# OpenEVSE_PLUS_v4.net
KiCad netlist of a schematic drawn in EAGLE
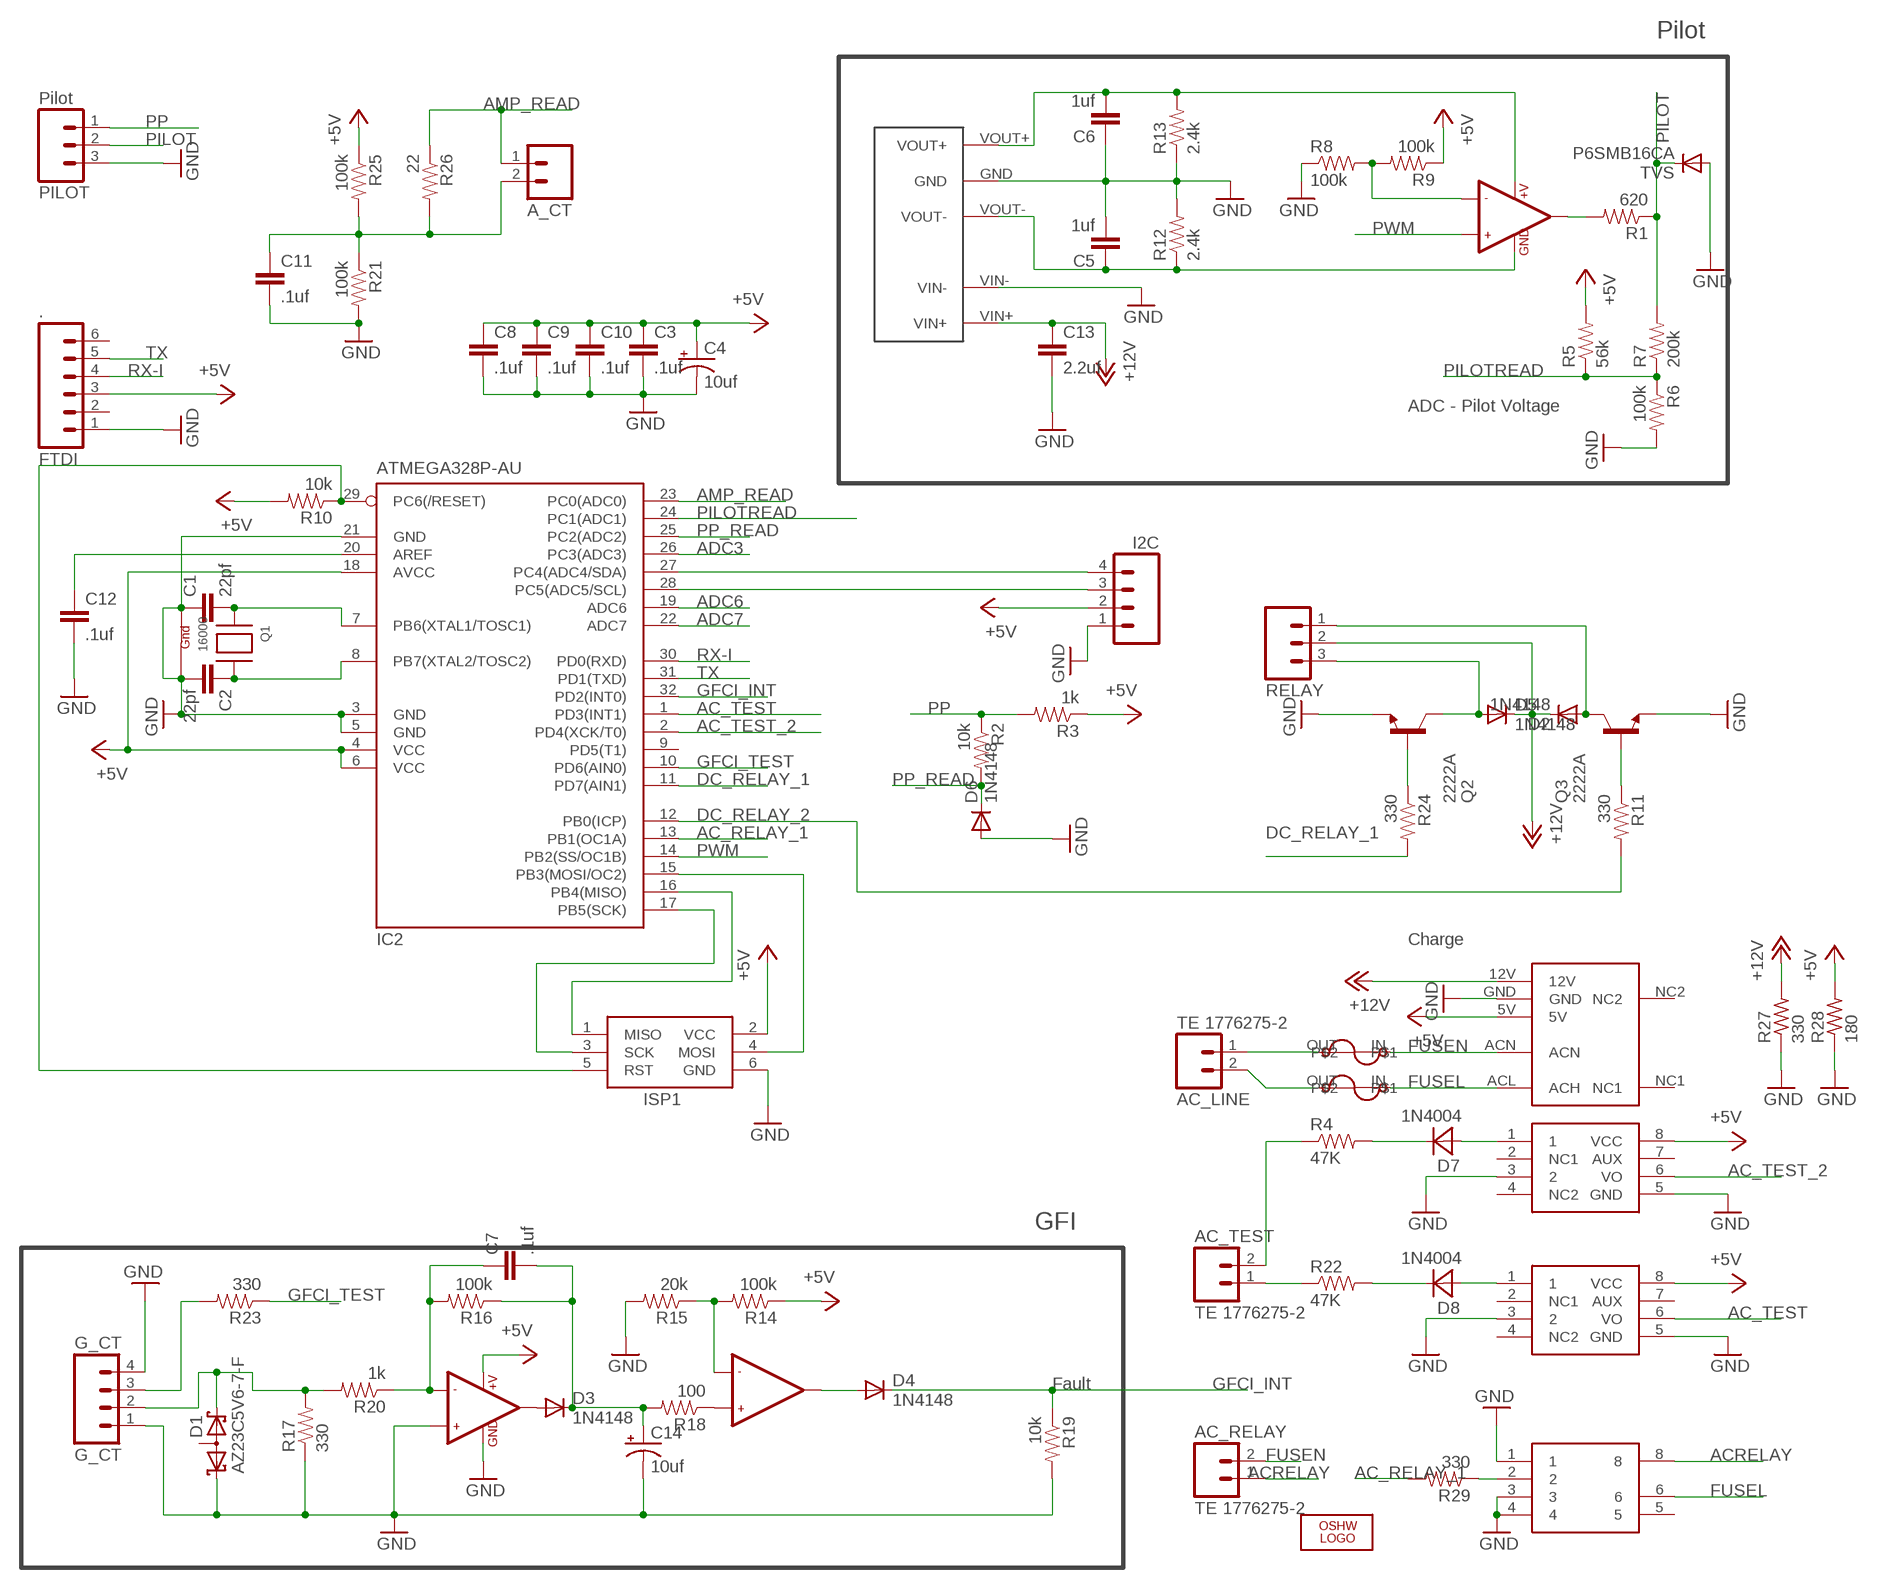
[diagram p0: schematic, sheet 1]

(export (version "E")
  (design (tool "Eeschema 10.0.6"))
  (components
    (comp (ref ".")
      (value "FTDI")
      (footprint "eagle-import:1X06_LOCK")
      (libsource (lib "eagle-import") (part "M06LOCK"))
    )
    (comp (ref "AC_LINE")
      (value "TE 1776275-2")
      (footprint "eagle-import:SCREWTERMINAL-3.5MM-2_LOCK")
      (libsource (lib "eagle-import") (part "M023.5MM_LOCK"))
    )
    (comp (ref "AC_RELAY")
      (value "TE 1776275-2")
      (footprint "eagle-import:SCREWTERMINAL-3.5MM-2_LOCK")
      (libsource (lib "eagle-import") (part "M023.5MM_LOCK"))
    )
    (comp (ref "AC_TEST")
      (value "TE 1776275-2")
      (footprint "eagle-import:SCREWTERMINAL-3.5MM-2_LOCK")
      (libsource (lib "eagle-import") (part "M023.5MM_LOCK"))
    )
    (comp (ref "A_CT")
      (value "M02PTH")
      (footprint "eagle-import:1X02")
      (libsource (lib "eagle-import") (part "M02PTH"))
    )
    (comp (ref "C1")
      (value "22pf")
      (footprint "eagle-import:0805")
      (libsource (lib "eagle-import") (part "CAP0805"))
    )
    (comp (ref "C2")
      (value "22pf")
      (footprint "eagle-import:0805")
      (libsource (lib "eagle-import") (part "CAP0805"))
    )
    (comp (ref "C3")
      (value ".1uf")
      (footprint "eagle-import:0805")
      (libsource (lib "eagle-import") (part "CAP0805"))
    )
    (comp (ref "C4")
      (value "10uf")
      (footprint "eagle-import:EIA3216")
      (libsource (lib "eagle-import") (part "CAP_POL1206"))
    )
    (comp (ref "C5")
      (value "1uf")
      (footprint "eagle-import:0805")
      (libsource (lib "eagle-import") (part "CAP0805"))
    )
    (comp (ref "C6")
      (value "1uf")
      (footprint "eagle-import:0805")
      (libsource (lib "eagle-import") (part "CAP0805"))
    )
    (comp (ref "C7")
      (value ".1uf")
      (footprint "eagle-import:0805")
      (libsource (lib "eagle-import") (part "CAP0805"))
    )
    (comp (ref "C8")
      (value ".1uf")
      (footprint "eagle-import:0805")
      (libsource (lib "eagle-import") (part "CAP0805"))
    )
    (comp (ref "C9")
      (value ".1uf")
      (footprint "eagle-import:0805")
      (libsource (lib "eagle-import") (part "CAP0805"))
    )
    (comp (ref "C10")
      (value ".1uf")
      (footprint "eagle-import:0805")
      (libsource (lib "eagle-import") (part "CAP0805"))
    )
    (comp (ref "C11")
      (value ".1uf")
      (footprint "eagle-import:0805")
      (libsource (lib "eagle-import") (part "CAP0805"))
    )
    (comp (ref "C12")
      (value ".1uf")
      (footprint "eagle-import:0805")
      (libsource (lib "eagle-import") (part "CAP0805"))
    )
    (comp (ref "C13")
      (value "2.2uf")
      (footprint "eagle-import:0805")
      (libsource (lib "eagle-import") (part "CAP0805"))
    )
    (comp (ref "C14")
      (value "10uf")
      (footprint "eagle-import:EIA3216")
      (libsource (lib "eagle-import") (part "CAP_POL1206"))
    )
    (comp (ref "D1")
      (value "AZ23C5V6-7-F")
      (footprint "eagle-import:SOT23")
      (libsource (lib "eagle-import") (part "BAS40-06"))
    )
    (comp (ref "D2")
      (value "1N4148")
      (footprint "eagle-import:SOD123")
      (libsource (lib "eagle-import") (part "DIODE-SOD123"))
    )
    (comp (ref "D3")
      (value "1N4148")
      (footprint "eagle-import:SOD123")
      (libsource (lib "eagle-import") (part "DIODE-SOD123"))
    )
    (comp (ref "D4")
      (value "1N4148")
      (footprint "eagle-import:SOD123")
      (libsource (lib "eagle-import") (part "DIODE-SOD123"))
    )
    (comp (ref "D5")
      (value "1N4148")
      (footprint "eagle-import:SOD123")
      (libsource (lib "eagle-import") (part "DIODE-SOD123"))
    )
    (comp (ref "D6")
      (value "1N4148")
      (footprint "eagle-import:SOD123")
      (libsource (lib "eagle-import") (part "DIODE-SOD123"))
    )
    (comp (ref "D7")
      (value "1N4004")
      (footprint "eagle-import:SMA")
      (libsource (lib "eagle-import") (part "MBRA340T3"))
    )
    (comp (ref "D8")
      (value "1N4004")
      (footprint "eagle-import:SMA")
      (libsource (lib "eagle-import") (part "MBRA340T3"))
    )
    (comp (ref "DCDC")
      (value "MD112D-12E")
      (footprint "eagle-import:DCDC_SIP")
      (libsource (lib "eagle-import") (part "DCDC_SIP"))
    )
    (comp (ref "F1")
      (value "BEL1AFUSE")
      (footprint "eagle-import:BELFUSE1A")
      (libsource (lib "eagle-import") (part "BEL1AFUSE"))
    )
    (comp (ref "F2")
      (value "BEL1AFUSE")
      (footprint "eagle-import:BELFUSE1A")
      (libsource (lib "eagle-import") (part "BEL1AFUSE"))
    )
    (comp (ref "G_CT")
      (value "G_CT")
      (footprint "eagle-import:1X04_LOCK")
      (libsource (lib "eagle-import") (part "M04LOCK"))
    )
    (comp (ref "I2C")
      (value "M04LOCK")
      (footprint "eagle-import:1X04_LOCK")
      (libsource (lib "eagle-import") (part "M04LOCK"))
    )
    (comp (ref "IC1")
      (value "MID400")
      (footprint "eagle-import:DIP08")
      (libsource (lib "eagle-import") (part "MID400"))
    )
    (comp (ref "IC2")
      (value "ATMEGA328P-AU")
      (footprint "eagle-import:TQFP32-08")
      (fields (field (name "MPN") "ATMEGA8-16AU"))
      (libsource (lib "eagle-import") (part "MEGA8-AI"))
    )
    (comp (ref "IC3")
      (value "LM358")
      (footprint "eagle-import:SO08")
      (libsource (lib "eagle-import") (part "LMV358"))
    )
    (comp (ref "IC4")
      (value "LF353")
      (footprint "eagle-import:SO08")
      (libsource (lib "eagle-import") (part "LMV358"))
    )
    (comp (ref "IC5")
      (value "AQH1213")
      (footprint "eagle-import:DIP7")
      (libsource (lib "eagle-import") (part "AQH1213"))
    )
    (comp (ref "IC6")
      (value "MID400")
      (footprint "eagle-import:DIP08")
      (libsource (lib "eagle-import") (part "MID400"))
    )
    (comp (ref "ISP1")
      (value "AVRISP-6")
      (footprint "eagle-import:AVRISP")
      (libsource (lib "eagle-import") (part "AVRISP-6"))
    )
    (comp (ref "LOGO1")
      (value "OSHW_LOGO_8MILX0150-NT")
      (footprint "eagle-import:OSHW_8X150_NOTEXT")
      (libsource (lib "eagle-import") (part "OSHW_LOGO_8MILX0150-NT"))
    )
    (comp (ref "PILOT")
      (value "Pilot")
      (footprint "eagle-import:SCREWTERMINAL-3.5MM-3_LOCK.007S")
      (libsource (lib "eagle-import") (part "M03SCREW_LOCK"))
    )
    (comp (ref "Q1")
      (value "16000")
      (footprint "eagle-import:NX3225")
      (libsource (lib "eagle-import") (part "XTAL-4-3225"))
    )
    (comp (ref "Q2")
      (value "2222A")
      (footprint "eagle-import:SOT23")
      (libsource (lib "eagle-import") (part "BCX70SMD"))
    )
    (comp (ref "Q3")
      (value "2222A")
      (footprint "eagle-import:SOT23")
      (libsource (lib "eagle-import") (part "BCX70SMD"))
    )
    (comp (ref "R1")
      (value "620")
      (footprint "eagle-import:0805")
      (libsource (lib "eagle-import") (part "RESISTOR0805-RES"))
    )
    (comp (ref "R2")
      (value "10k")
      (footprint "eagle-import:0805")
      (libsource (lib "eagle-import") (part "RESISTOR0805-RES"))
    )
    (comp (ref "R3")
      (value "1k")
      (footprint "eagle-import:0805")
      (libsource (lib "eagle-import") (part "RESISTOR0805-RES"))
    )
    (comp (ref "R4")
      (value "47K")
      (footprint "eagle-import:AXIAL-0.4")
      (libsource (lib "eagle-import") (part "RESISTORPTH-1/4W"))
    )
    (comp (ref "R5")
      (value "56k")
      (footprint "eagle-import:0805")
      (libsource (lib "eagle-import") (part "RESISTOR0805-RES"))
    )
    (comp (ref "R6")
      (value "100k")
      (footprint "eagle-import:0805")
      (libsource (lib "eagle-import") (part "RESISTOR0805-RES"))
    )
    (comp (ref "R7")
      (value "200k")
      (footprint "eagle-import:0805")
      (libsource (lib "eagle-import") (part "RESISTOR0805-RES"))
    )
    (comp (ref "R8")
      (value "100k")
      (footprint "eagle-import:0805")
      (libsource (lib "eagle-import") (part "RESISTOR0805-RES"))
    )
    (comp (ref "R9")
      (value "100k")
      (footprint "eagle-import:0805")
      (libsource (lib "eagle-import") (part "RESISTOR0805-RES"))
    )
    (comp (ref "R10")
      (value "10k")
      (footprint "eagle-import:0805")
      (libsource (lib "eagle-import") (part "RESISTOR0805-RES"))
    )
    (comp (ref "R11")
      (value "330")
      (footprint "eagle-import:0805")
      (libsource (lib "eagle-import") (part "RESISTOR0805-RES"))
    )
    (comp (ref "R12")
      (value "2.4k")
      (footprint "eagle-import:0805")
      (libsource (lib "eagle-import") (part "RESISTOR0805-RES"))
    )
    (comp (ref "R13")
      (value "2.4k")
      (footprint "eagle-import:0805")
      (libsource (lib "eagle-import") (part "RESISTOR0805-RES"))
    )
    (comp (ref "R14")
      (value "100k")
      (footprint "eagle-import:0805")
      (libsource (lib "eagle-import") (part "RESISTOR0805-RES"))
    )
    (comp (ref "R15")
      (value "20k")
      (footprint "eagle-import:0805")
      (libsource (lib "eagle-import") (part "RESISTOR0805-RES"))
    )
    (comp (ref "R16")
      (value "100k")
      (footprint "eagle-import:0805")
      (libsource (lib "eagle-import") (part "RESISTOR0805-RES"))
    )
    (comp (ref "R17")
      (value "330")
      (footprint "eagle-import:0805")
      (libsource (lib "eagle-import") (part "RESISTOR0805-RES"))
    )
    (comp (ref "R18")
      (value "100")
      (footprint "eagle-import:0805")
      (libsource (lib "eagle-import") (part "RESISTOR0805-RES"))
    )
    (comp (ref "R19")
      (value "10k")
      (footprint "eagle-import:0805")
      (libsource (lib "eagle-import") (part "RESISTOR0805-RES"))
    )
    (comp (ref "R20")
      (value "1k")
      (footprint "eagle-import:0805")
      (libsource (lib "eagle-import") (part "RESISTOR0805-RES"))
    )
    (comp (ref "R21")
      (value "100k")
      (footprint "eagle-import:0805")
      (libsource (lib "eagle-import") (part "RESISTOR0805-RES"))
    )
    (comp (ref "R22")
      (value "47K")
      (footprint "eagle-import:AXIAL-0.4")
      (libsource (lib "eagle-import") (part "RESISTORPTH-1/4W"))
    )
    (comp (ref "R23")
      (value "330")
      (footprint "eagle-import:0805")
      (libsource (lib "eagle-import") (part "RESISTOR0805-RES"))
    )
    (comp (ref "R24")
      (value "330")
      (footprint "eagle-import:0805")
      (libsource (lib "eagle-import") (part "RESISTOR0805-RES"))
    )
    (comp (ref "R25")
      (value "100k")
      (footprint "eagle-import:0805")
      (libsource (lib "eagle-import") (part "RESISTOR0805-RES"))
    )
    (comp (ref "R26")
      (value "22")
      (footprint "eagle-import:0805")
      (libsource (lib "eagle-import") (part "RESISTOR0805-RES"))
    )
    (comp (ref "R27")
      (value "330")
      (footprint "eagle-import:R1206")
      (libsource (lib "eagle-import") (part "R-US_R1206"))
    )
    (comp (ref "R28")
      (value "180")
      (footprint "eagle-import:R1206")
      (libsource (lib "eagle-import") (part "R-US_R1206"))
    )
    (comp (ref "R29")
      (value "330")
      (footprint "eagle-import:0805")
      (libsource (lib "eagle-import") (part "RESISTOR0805-RES"))
    )
    (comp (ref "RELAY")
      (value "M03SCREW_LOCK")
      (footprint "eagle-import:SCREWTERMINAL-3.5MM-3_LOCK.007S")
      (libsource (lib "eagle-import") (part "M03SCREW_LOCK"))
    )
    (comp (ref "TVS")
      (value "P6SMB16CA")
      (footprint "eagle-import:SMB")
      (libsource (lib "eagle-import") (part "DIODE-SMB"))
    )
    (comp (ref "U$1")
      (value "MPM-04E-1205")
      (footprint "eagle-import:MPM-04E-1205")
      (libsource (lib "eagle-import") (part "MPM-04E-1205"))
    )
  )
  (nets
    (net (code "1") (name "+5V") (class "Default")
      (node (ref ".") (pin "3") (pinfunction "3_3") (pintype "passive"))
      (node (ref "C10") (pin "1") (pinfunction "1_1") (pintype "passive"))
      (node (ref "C3") (pin "1") (pinfunction "1_1") (pintype "passive"))
      (node (ref "C4") (pin "A") (pinfunction "+_A") (pintype "passive"))
      (node (ref "C8") (pin "1") (pinfunction "1_1") (pintype "passive"))
      (node (ref "C9") (pin "1") (pinfunction "1_1") (pintype "passive"))
      (node (ref "I2C") (pin "2") (pinfunction "2_2") (pintype "passive"))
      (node (ref "IC1") (pin "8") (pinfunction "VCC_8") (pintype "bidirectional"))
      (node (ref "IC2") (pin "18") (pinfunction "AVCC_18") (pintype "power_in"))
      (node (ref "IC2") (pin "4") (pinfunction "VCC_4") (pintype "power_in"))
      (node (ref "IC2") (pin "6") (pinfunction "VCC_6") (pintype "power_in"))
      (node (ref "IC3") (pin "8") (pinfunction "+V_8") (pintype "power_in"))
      (node (ref "IC6") (pin "8") (pinfunction "VCC_8") (pintype "bidirectional"))
      (node (ref "ISP1") (pin "2") (pinfunction "VCC_2") (pintype "power_in"))
      (node (ref "R10") (pin "2") (pinfunction "2_2") (pintype "passive"))
      (node (ref "R14") (pin "1") (pinfunction "1_1") (pintype "passive"))
      (node (ref "R25") (pin "1") (pinfunction "1_1") (pintype "passive"))
      (node (ref "R28") (pin "2") (pinfunction "2_2") (pintype "passive"))
      (node (ref "R3") (pin "1") (pinfunction "1_1") (pintype "passive"))
      (node (ref "R5") (pin "2") (pinfunction "2_2") (pintype "passive"))
      (node (ref "R9") (pin "1") (pinfunction "1_1") (pintype "passive"))
      (node (ref "U$1") (pin "5V") (pinfunction "5V_5V") (pintype "bidirectional"))
    )
    (net (code "2") (name "+12V") (class "Default")
      (node (ref "C13") (pin "1") (pinfunction "1_1") (pintype "passive"))
      (node (ref "D2") (pin "C") (pinfunction "C_C") (pintype "passive"))
      (node (ref "D5") (pin "C") (pinfunction "C_C") (pintype "passive"))
      (node (ref "DCDC") (pin "VIN+") (pinfunction "VIN+_VIN+") (pintype "bidirectional"))
      (node (ref "R27") (pin "2") (pinfunction "2_2") (pintype "passive"))
      (node (ref "RELAY") (pin "2") (pinfunction "2_2") (pintype "passive"))
      (node (ref "U$1") (pin "12V") (pinfunction "12V_12V") (pintype "bidirectional"))
    )
    (net (code "3") (name "/ACRELAY") (class "Default")
      (node (ref "AC_RELAY") (pin "1") (pinfunction "1_1") (pintype "passive"))
      (node (ref "IC5") (pin "8") (pinfunction "8_8") (pintype "bidirectional"))
    )
    (net (code "4") (name "/AC_RELAY_1") (class "Default")
      (node (ref "IC2") (pin "13") (pinfunction "PB1(OC1A)_13") (pintype "bidirectional"))
      (node (ref "R29") (pin "2") (pinfunction "2_2") (pintype "passive"))
    )
    (net (code "5") (name "/AC_TEST") (class "Default")
      (node (ref "IC2") (pin "1") (pinfunction "PD3(INT1)_1") (pintype "bidirectional"))
      (node (ref "IC6") (pin "6") (pinfunction "VO_6") (pintype "bidirectional"))
    )
    (net (code "6") (name "/AC_TEST_2") (class "Default")
      (node (ref "IC1") (pin "6") (pinfunction "VO_6") (pintype "bidirectional"))
      (node (ref "IC2") (pin "2") (pinfunction "PD4(XCK/T0)_2") (pintype "bidirectional"))
    )
    (net (code "7") (name "/ADC3") (class "Default")
      (node (ref "IC2") (pin "26") (pinfunction "PC3(ADC3)_26") (pintype "bidirectional"))
    )
    (net (code "8") (name "/ADC6") (class "Default")
      (node (ref "IC2") (pin "19") (pinfunction "ADC6_19") (pintype "bidirectional"))
    )
    (net (code "9") (name "/ADC7") (class "Default")
      (node (ref "IC2") (pin "22") (pinfunction "ADC7_22") (pintype "bidirectional"))
    )
    (net (code "10") (name "/AMP_READ") (class "Default")
      (node (ref "A_CT") (pin "1") (pinfunction "1_1") (pintype "passive"))
      (node (ref "IC2") (pin "23") (pinfunction "PC0(ADC0)_23") (pintype "bidirectional"))
      (node (ref "R26") (pin "1") (pinfunction "1_1") (pintype "passive"))
    )
    (net (code "11") (name "/DC_RELAY_1") (class "Default")
      (node (ref "IC2") (pin "11") (pinfunction "PD7(AIN1)_11") (pintype "bidirectional"))
      (node (ref "R24") (pin "2") (pinfunction "2_2") (pintype "passive"))
    )
    (net (code "12") (name "/DC_RELAY_2") (class "Default")
      (node (ref "IC2") (pin "12") (pinfunction "PB0(ICP)_12") (pintype "bidirectional"))
      (node (ref "R11") (pin "2") (pinfunction "2_2") (pintype "passive"))
    )
    (net (code "13") (name "/FUSEL") (class "Default")
      (node (ref "F2") (pin "IN") (pinfunction "P$2_IN") (pintype "bidirectional"))
      (node (ref "IC5") (pin "6") (pinfunction "6_6") (pintype "bidirectional"))
      (node (ref "U$1") (pin "ACL") (pinfunction "ACH_ACL") (pintype "bidirectional"))
    )
    (net (code "14") (name "/FUSEN") (class "Default")
      (node (ref "AC_RELAY") (pin "2") (pinfunction "2_2") (pintype "passive"))
      (node (ref "F1") (pin "IN") (pinfunction "P$2_IN") (pintype "bidirectional"))
      (node (ref "U$1") (pin "ACN") (pinfunction "ACN_ACN") (pintype "bidirectional"))
    )
    (net (code "15") (name "/GFCI_INT") (class "Default")
      (node (ref "D4") (pin "C") (pinfunction "C_C") (pintype "passive"))
      (node (ref "IC2") (pin "32") (pinfunction "PD2(INT0)_32") (pintype "bidirectional"))
      (node (ref "R19") (pin "1") (pinfunction "1_1") (pintype "passive"))
    )
    (net (code "16") (name "/GFCI_TEST") (class "Default")
      (node (ref "IC2") (pin "10") (pinfunction "PD6(AIN0)_10") (pintype "bidirectional"))
      (node (ref "R23") (pin "1") (pinfunction "1_1") (pintype "passive"))
    )
    (net (code "17") (name "/PILOT") (class "Default")
      (node (ref "PILOT") (pin "2") (pinfunction "2_2") (pintype "passive"))
      (node (ref "R1") (pin "1") (pinfunction "1_1") (pintype "passive"))
      (node (ref "R7") (pin "2") (pinfunction "2_2") (pintype "passive"))
      (node (ref "TVS") (pin "C") (pinfunction "C_C") (pintype "passive"))
    )
    (net (code "18") (name "/PILOTREAD") (class "Default")
      (node (ref "IC2") (pin "24") (pinfunction "PC1(ADC1)_24") (pintype "bidirectional"))
      (node (ref "R5") (pin "1") (pinfunction "1_1") (pintype "passive"))
      (node (ref "R6") (pin "1") (pinfunction "1_1") (pintype "passive"))
      (node (ref "R7") (pin "1") (pinfunction "1_1") (pintype "passive"))
    )
    (net (code "19") (name "/PP") (class "Default")
      (node (ref "PILOT") (pin "1") (pinfunction "1_1") (pintype "passive"))
      (node (ref "R2") (pin "1") (pinfunction "1_1") (pintype "passive"))
      (node (ref "R3") (pin "2") (pinfunction "2_2") (pintype "passive"))
    )
    (net (code "20") (name "/PP_READ") (class "Default")
      (node (ref "D6") (pin "C") (pinfunction "C_C") (pintype "passive"))
      (node (ref "IC2") (pin "25") (pinfunction "PC2(ADC2)_25") (pintype "bidirectional"))
      (node (ref "R2") (pin "2") (pinfunction "2_2") (pintype "passive"))
    )
    (net (code "21") (name "/PWM") (class "Default")
      (node (ref "IC2") (pin "14") (pinfunction "PB2(SS/OC1B)_14") (pintype "bidirectional"))
      (node (ref "IC4") (pin "3") (pinfunction "+IN1_3") (pintype "input"))
    )
    (net (code "22") (name "/RX-I") (class "Default")
      (node (ref ".") (pin "4") (pinfunction "4_4") (pintype "passive"))
      (node (ref "IC2") (pin "30") (pinfunction "PD0(RXD)_30") (pintype "bidirectional"))
    )
    (net (code "23") (name "/TX") (class "Default")
      (node (ref ".") (pin "5") (pinfunction "5_5") (pintype "passive"))
      (node (ref "IC2") (pin "31") (pinfunction "PD1(TXD)_31") (pintype "bidirectional"))
    )
    (net (code "24") (name "GND") (class "Default")
      (node (ref ".") (pin "1") (pinfunction "1_1") (pintype "passive"))
      (node (ref "C1") (pin "1") (pinfunction "1_1") (pintype "passive"))
      (node (ref "C10") (pin "2") (pinfunction "2_2") (pintype "passive"))
      (node (ref "C11") (pin "2") (pinfunction "2_2") (pintype "passive"))
      (node (ref "C12") (pin "2") (pinfunction "2_2") (pintype "passive"))
      (node (ref "C13") (pin "2") (pinfunction "2_2") (pintype "passive"))
      (node (ref "C14") (pin "C") (pinfunction "-_C") (pintype "passive"))
      (node (ref "C2") (pin "2") (pinfunction "2_2") (pintype "passive"))
      (node (ref "C3") (pin "2") (pinfunction "2_2") (pintype "passive"))
      (node (ref "C4") (pin "C") (pinfunction "-_C") (pintype "passive"))
      (node (ref "C5") (pin "2") (pinfunction "2_2") (pintype "passive"))
      (node (ref "C6") (pin "1") (pinfunction "1_1") (pintype "passive"))
      (node (ref "C8") (pin "2") (pinfunction "2_2") (pintype "passive"))
      (node (ref "C9") (pin "2") (pinfunction "2_2") (pintype "passive"))
      (node (ref "D1") (pin "1") (pinfunction "K1_1") (pintype "passive"))
      (node (ref "D6") (pin "A") (pinfunction "A_A") (pintype "passive"))
      (node (ref "DCDC") (pin "GND") (pinfunction "GND_GND") (pintype "bidirectional"))
      (node (ref "DCDC") (pin "VIN-") (pinfunction "VIN-_VIN-") (pintype "bidirectional"))
      (node (ref "G_CT") (pin "1") (pinfunction "1_1") (pintype "passive"))
      (node (ref "G_CT") (pin "4") (pinfunction "4_4") (pintype "passive"))
      (node (ref "I2C") (pin "1") (pinfunction "1_1") (pintype "passive"))
      (node (ref "IC1") (pin "3") (pinfunction "2_3") (pintype "bidirectional"))
      (node (ref "IC1") (pin "5") (pinfunction "GND_5") (pintype "bidirectional"))
      (node (ref "IC2") (pin "21") (pinfunction "GND_21") (pintype "power_in"))
      (node (ref "IC2") (pin "3") (pinfunction "GND_3") (pintype "power_in"))
      (node (ref "IC2") (pin "5") (pinfunction "GND_5") (pintype "power_in"))
      (node (ref "IC3") (pin "3") (pinfunction "+IN1_3") (pintype "input"))
      (node (ref "IC3") (pin "4") (pinfunction "GND_4") (pintype "power_in"))
      (node (ref "IC5") (pin "1") (pinfunction "1_1") (pintype "bidirectional"))
      (node (ref "IC5") (pin "3") (pinfunction "3_3") (pintype "bidirectional"))
      (node (ref "IC5") (pin "4") (pinfunction "4_4") (pintype "bidirectional"))
      (node (ref "IC6") (pin "3") (pinfunction "2_3") (pintype "bidirectional"))
      (node (ref "IC6") (pin "5") (pinfunction "GND_5") (pintype "bidirectional"))
      (node (ref "ISP1") (pin "6") (pinfunction "GND_6") (pintype "power_in"))
      (node (ref "PILOT") (pin "3") (pinfunction "3_3") (pintype "passive"))
      (node (ref "Q1") (pin "1") (pinfunction "G1_1") (pintype "power_in"))
      (node (ref "Q1") (pin "3") (pinfunction "G2_3") (pintype "power_in"))
      (node (ref "Q2") (pin "2") (pinfunction "E_2") (pintype "passive"))
      (node (ref "Q3") (pin "2") (pinfunction "E_2") (pintype "passive"))
      (node (ref "R12") (pin "2") (pinfunction "2_2") (pintype "passive"))
      (node (ref "R13") (pin "1") (pinfunction "1_1") (pintype "passive"))
      (node (ref "R15") (pin "2") (pinfunction "2_2") (pintype "passive"))
      (node (ref "R17") (pin "1") (pinfunction "1_1") (pintype "passive"))
      (node (ref "R19") (pin "2") (pinfunction "2_2") (pintype "passive"))
      (node (ref "R21") (pin "2") (pinfunction "2_2") (pintype "passive"))
      (node (ref "R27") (pin "1") (pinfunction "1_1") (pintype "passive"))
      (node (ref "R28") (pin "1") (pinfunction "1_1") (pintype "passive"))
      (node (ref "R6") (pin "2") (pinfunction "2_2") (pintype "passive"))
      (node (ref "R8") (pin "1") (pinfunction "1_1") (pintype "passive"))
      (node (ref "TVS") (pin "A") (pinfunction "A_A") (pintype "passive"))
      (node (ref "U$1") (pin "GND") (pinfunction "GND_GND") (pintype "bidirectional"))
    )
    (net (code "25") (name "Net-(A_CT-Pad2)") (class "Default")
      (node (ref "A_CT") (pin "2") (pinfunction "2_2") (pintype "passive"))
      (node (ref "C11") (pin "1") (pinfunction "1_1") (pintype "passive"))
      (node (ref "R21") (pin "1") (pinfunction "1_1") (pintype "passive"))
      (node (ref "R25") (pin "2") (pinfunction "2_2") (pintype "passive"))
      (node (ref "R26") (pin "2") (pinfunction "2_2") (pintype "passive"))
    )
    (net (code "26") (name "Net-(C14-+)") (class "Default")
      (node (ref "C14") (pin "A") (pinfunction "+_A") (pintype "passive"))
      (node (ref "C7") (pin "2") (pinfunction "2_2") (pintype "passive"))
      (node (ref "D3") (pin "C") (pinfunction "C_C") (pintype "passive"))
      (node (ref "R16") (pin "1") (pinfunction "1_1") (pintype "passive"))
      (node (ref "R18") (pin "2") (pinfunction "2_2") (pintype "passive"))
    )
    (net (code "27") (name "Net-(D1-K2)") (class "Default")
      (node (ref "D1") (pin "2") (pinfunction "K2_2") (pintype "passive"))
      (node (ref "G_CT") (pin "2") (pinfunction "2_2") (pintype "passive"))
      (node (ref "R17") (pin "2") (pinfunction "2_2") (pintype "passive"))
      (node (ref "R20") (pin "2") (pinfunction "2_2") (pintype "passive"))
    )
    (net (code "28") (name "Net-(D7-PadA)") (class "Default")
      (node (ref "D7") (pin "A") (pinfunction "A_A") (pintype "passive"))
      (node (ref "IC1") (pin "1") (pinfunction "1_1") (pintype "bidirectional"))
    )
    (net (code "29") (name "Net-(D8-PadA)") (class "Default")
      (node (ref "D8") (pin "A") (pinfunction "A_A") (pintype "passive"))
      (node (ref "IC6") (pin "1") (pinfunction "1_1") (pintype "bidirectional"))
    )
    (net (code "30") (name "Net-(F1-P$1)") (class "Default")
      (node (ref "AC_LINE") (pin "1") (pinfunction "1_1") (pintype "passive"))
      (node (ref "F1") (pin "OUT") (pinfunction "P$1_OUT") (pintype "bidirectional"))
    )
    (net (code "31") (name "Net-(F2-P$1)") (class "Default")
      (node (ref "AC_LINE") (pin "2") (pinfunction "2_2") (pintype "passive"))
      (node (ref "F2") (pin "OUT") (pinfunction "P$1_OUT") (pintype "bidirectional"))
    )
    (net (code "32") (name "Net-(G_CT-Pad3)") (class "Default")
      (node (ref "G_CT") (pin "3") (pinfunction "3_3") (pintype "passive"))
      (node (ref "R23") (pin "2") (pinfunction "2_2") (pintype "passive"))
    )
    (net (code "33") (name "Net-(IC2-AREF)") (class "Default")
      (node (ref "C12") (pin "1") (pinfunction "1_1") (pintype "passive"))
      (node (ref "IC2") (pin "20") (pinfunction "AREF_20") (pintype "passive"))
    )
    (net (code "34") (name "Net-(IC2-PB3(MOSI{slash}OC2))") (class "Default")
      (node (ref "IC2") (pin "15") (pinfunction "PB3(MOSI/OC2)_15") (pintype "bidirectional"))
      (node (ref "ISP1") (pin "4") (pinfunction "MOSI_4") (pintype "output"))
    )
    (net (code "35") (name "Net-(IC2-PB4(MISO))") (class "Default")
      (node (ref "IC2") (pin "16") (pinfunction "PB4(MISO)_16") (pintype "bidirectional"))
      (node (ref "ISP1") (pin "1") (pinfunction "MISO_1") (pintype "input"))
    )
    (net (code "36") (name "Net-(IC2-PB5(SCK))") (class "Default")
      (node (ref "IC2") (pin "17") (pinfunction "PB5(SCK)_17") (pintype "bidirectional"))
      (node (ref "ISP1") (pin "3") (pinfunction "SCK_3") (pintype "output"))
    )
    (net (code "37") (name "Net-(IC2-PB6(XTAL1{slash}TOSC1))") (class "Default")
      (node (ref "C1") (pin "2") (pinfunction "2_2") (pintype "passive"))
      (node (ref "IC2") (pin "7") (pinfunction "PB6(XTAL1/TOSC1)_7") (pintype "bidirectional"))
      (node (ref "Q1") (pin "2") (pinfunction "X1_2") (pintype "bidirectional"))
    )
    (net (code "38") (name "Net-(IC2-PB7(XTAL2{slash}TOSC2))") (class "Default")
      (node (ref "C2") (pin "1") (pinfunction "1_1") (pintype "passive"))
      (node (ref "IC2") (pin "8") (pinfunction "PB7(XTAL2/TOSC2)_8") (pintype "bidirectional"))
      (node (ref "Q1") (pin "4") (pinfunction "X2_4") (pintype "bidirectional"))
    )
    (net (code "39") (name "Net-(IC2-PC4(ADC4{slash}SDA))") (class "Default")
      (node (ref "I2C") (pin "4") (pinfunction "4_4") (pintype "passive"))
      (node (ref "IC2") (pin "27") (pinfunction "PC4(ADC4/SDA)_27") (pintype "bidirectional"))
    )
    (net (code "40") (name "Net-(IC2-PC5(ADC5{slash}SCL))") (class "Default")
      (node (ref "I2C") (pin "3") (pinfunction "3_3") (pintype "passive"))
      (node (ref "IC2") (pin "28") (pinfunction "PC5(ADC5/SCL)_28") (pintype "bidirectional"))
    )
    (net (code "41") (name "Net-(IC2-PC6({slash}RESET))") (class "Default")
      (node (ref "IC2") (pin "29") (pinfunction "PC6(/RESET)_29") (pintype "bidirectional"))
      (node (ref "ISP1") (pin "5") (pinfunction "RST_5") (pintype "output"))
      (node (ref "R10") (pin "1") (pinfunction "1_1") (pintype "passive"))
    )
    (net (code "42") (name "Net-(IC3A--IN1)") (class "Default")
      (node (ref "C7") (pin "1") (pinfunction "1_1") (pintype "passive"))
      (node (ref "IC3") (pin "2") (pinfunction "-IN1_2") (pintype "input"))
      (node (ref "R16") (pin "2") (pinfunction "2_2") (pintype "passive"))
      (node (ref "R20") (pin "1") (pinfunction "1_1") (pintype "passive"))
    )
    (net (code "43") (name "Net-(IC3A-OUT1)") (class "Default")
      (node (ref "D3") (pin "A") (pinfunction "A_A") (pintype "passive"))
      (node (ref "IC3") (pin "1") (pinfunction "OUT1_1") (pintype "output"))
    )
    (net (code "44") (name "Net-(IC3B-+IN2)") (class "Default")
      (node (ref "IC3") (pin "5") (pinfunction "+IN2_5") (pintype "input"))
      (node (ref "R18") (pin "1") (pinfunction "1_1") (pintype "passive"))
    )
    (net (code "45") (name "Net-(IC3B--IN2)") (class "Default")
      (node (ref "IC3") (pin "6") (pinfunction "-IN2_6") (pintype "input"))
      (node (ref "R14") (pin "2") (pinfunction "2_2") (pintype "passive"))
      (node (ref "R15") (pin "1") (pinfunction "1_1") (pintype "passive"))
    )
    (net (code "46") (name "Net-(IC3B-OUT2)") (class "Default")
      (node (ref "D4") (pin "A") (pinfunction "A_A") (pintype "passive"))
      (node (ref "IC3") (pin "7") (pinfunction "OUT2_7") (pintype "output"))
    )
    (net (code "47") (name "Net-(IC4A-+V)") (class "Default")
      (node (ref "C6") (pin "2") (pinfunction "2_2") (pintype "passive"))
      (node (ref "DCDC") (pin "VOUT+") (pinfunction "VOUT+_VOUT+") (pintype "bidirectional"))
      (node (ref "IC4") (pin "8") (pinfunction "+V_8") (pintype "power_in"))
      (node (ref "R13") (pin "2") (pinfunction "2_2") (pintype "passive"))
    )
    (net (code "48") (name "Net-(IC4A--IN1)") (class "Default")
      (node (ref "IC4") (pin "2") (pinfunction "-IN1_2") (pintype "input"))
      (node (ref "R8") (pin "2") (pinfunction "2_2") (pintype "passive"))
      (node (ref "R9") (pin "2") (pinfunction "2_2") (pintype "passive"))
    )
    (net (code "49") (name "Net-(IC4A-GND)") (class "Default")
      (node (ref "C5") (pin "1") (pinfunction "1_1") (pintype "passive"))
      (node (ref "DCDC") (pin "VOUT-") (pinfunction "VOUT-_VOUT-") (pintype "bidirectional"))
      (node (ref "IC4") (pin "4") (pinfunction "GND_4") (pintype "power_in"))
      (node (ref "R12") (pin "1") (pinfunction "1_1") (pintype "passive"))
    )
    (net (code "50") (name "Net-(IC4A-OUT1)") (class "Default")
      (node (ref "IC4") (pin "1") (pinfunction "OUT1_1") (pintype "output"))
      (node (ref "R1") (pin "2") (pinfunction "2_2") (pintype "passive"))
    )
    (net (code "51") (name "Net-(IC5-Pad2)") (class "Default")
      (node (ref "IC5") (pin "2") (pinfunction "2_2") (pintype "bidirectional"))
      (node (ref "R29") (pin "1") (pinfunction "1_1") (pintype "passive"))
    )
    (net (code "52") (name "Net-(Q2-B)") (class "Default")
      (node (ref "Q2") (pin "1") (pinfunction "B_1") (pintype "passive"))
      (node (ref "R24") (pin "1") (pinfunction "1_1") (pintype "passive"))
    )
    (net (code "53") (name "Net-(Q2-C)") (class "Default")
      (node (ref "D5") (pin "A") (pinfunction "A_A") (pintype "passive"))
      (node (ref "Q2") (pin "3") (pinfunction "C_3") (pintype "passive"))
      (node (ref "RELAY") (pin "3") (pinfunction "3_3") (pintype "passive"))
    )
    (net (code "54") (name "Net-(Q3-B)") (class "Default")
      (node (ref "Q3") (pin "1") (pinfunction "B_1") (pintype "passive"))
      (node (ref "R11") (pin "1") (pinfunction "1_1") (pintype "passive"))
    )
    (net (code "55") (name "Net-(Q3-C)") (class "Default")
      (node (ref "D2") (pin "A") (pinfunction "A_A") (pintype "passive"))
      (node (ref "Q3") (pin "3") (pinfunction "C_3") (pintype "passive"))
      (node (ref "RELAY") (pin "1") (pinfunction "1_1") (pintype "passive"))
    )
    (net (code "56") (name "Net-(R4-1)") (class "Default")
      (node (ref "AC_TEST") (pin "2") (pinfunction "2_2") (pintype "passive"))
      (node (ref "R4") (pin "P$1") (pinfunction "1_P$1") (pintype "passive"))
    )
    (net (code "57") (name "Net-(R4-2)") (class "Default")
      (node (ref "D7") (pin "C") (pinfunction "C_C") (pintype "passive"))
      (node (ref "R4") (pin "P$2") (pinfunction "2_P$2") (pintype "passive"))
    )
    (net (code "58") (name "Net-(R22-1)") (class "Default")
      (node (ref "AC_TEST") (pin "1") (pinfunction "1_1") (pintype "passive"))
      (node (ref "R22") (pin "P$1") (pinfunction "1_P$1") (pintype "passive"))
    )
    (net (code "59") (name "Net-(R22-2)") (class "Default")
      (node (ref "D8") (pin "C") (pinfunction "C_C") (pintype "passive"))
      (node (ref "R22") (pin "P$2") (pinfunction "2_P$2") (pintype "passive"))
    )
    (net (code "60") (name "unconnected-(.-Pad2)") (class "Default")
      (node (ref ".") (pin "2") (pinfunction "2_2") (pintype "passive"))
    )
    (net (code "61") (name "unconnected-(.-Pad6)") (class "Default")
      (node (ref ".") (pin "6") (pinfunction "6_6") (pintype "passive"))
    )
    (net (code "62") (name "unconnected-(D1-AA-Pad3)") (class "Default")
      (node (ref "D1") (pin "3") (pinfunction "AA_3") (pintype "passive"))
    )
    (net (code "63") (name "unconnected-(IC1-AUX-Pad7)") (class "Default")
      (node (ref "IC1") (pin "7") (pinfunction "AUX_7") (pintype "bidirectional"))
    )
    (net (code "64") (name "unconnected-(IC1-NC1-Pad2)") (class "Default")
      (node (ref "IC1") (pin "2") (pinfunction "NC1_2") (pintype "bidirectional"))
    )
    (net (code "65") (name "unconnected-(IC1-NC2-Pad4)") (class "Default")
      (node (ref "IC1") (pin "4") (pinfunction "NC2_4") (pintype "bidirectional"))
    )
    (net (code "66") (name "unconnected-(IC2-PD5(T1)-Pad9)") (class "Default")
      (node (ref "IC2") (pin "9") (pinfunction "PD5(T1)_9") (pintype "bidirectional"))
    )
    (net (code "67") (name "unconnected-(IC5-Pad5)") (class "Default")
      (node (ref "IC5") (pin "5") (pinfunction "5_5") (pintype "bidirectional"))
    )
    (net (code "68") (name "unconnected-(IC6-AUX-Pad7)") (class "Default")
      (node (ref "IC6") (pin "7") (pinfunction "AUX_7") (pintype "bidirectional"))
    )
    (net (code "69") (name "unconnected-(IC6-NC1-Pad2)") (class "Default")
      (node (ref "IC6") (pin "2") (pinfunction "NC1_2") (pintype "bidirectional"))
    )
    (net (code "70") (name "unconnected-(IC6-NC2-Pad4)") (class "Default")
      (node (ref "IC6") (pin "4") (pinfunction "NC2_4") (pintype "bidirectional"))
    )
    (net (code "71") (name "unconnected-(U$1-PadNC1)") (class "Default")
      (node (ref "U$1") (pin "NC1") (pinfunction "NC1_NC1") (pintype "bidirectional"))
    )
    (net (code "72") (name "unconnected-(U$1-PadNC2)") (class "Default")
      (node (ref "U$1") (pin "NC2") (pinfunction "NC2_NC2") (pintype "bidirectional"))
    )
  )
)
